# WGSwitch.net
KiCad netlist of a schematic drawn in EAGLE
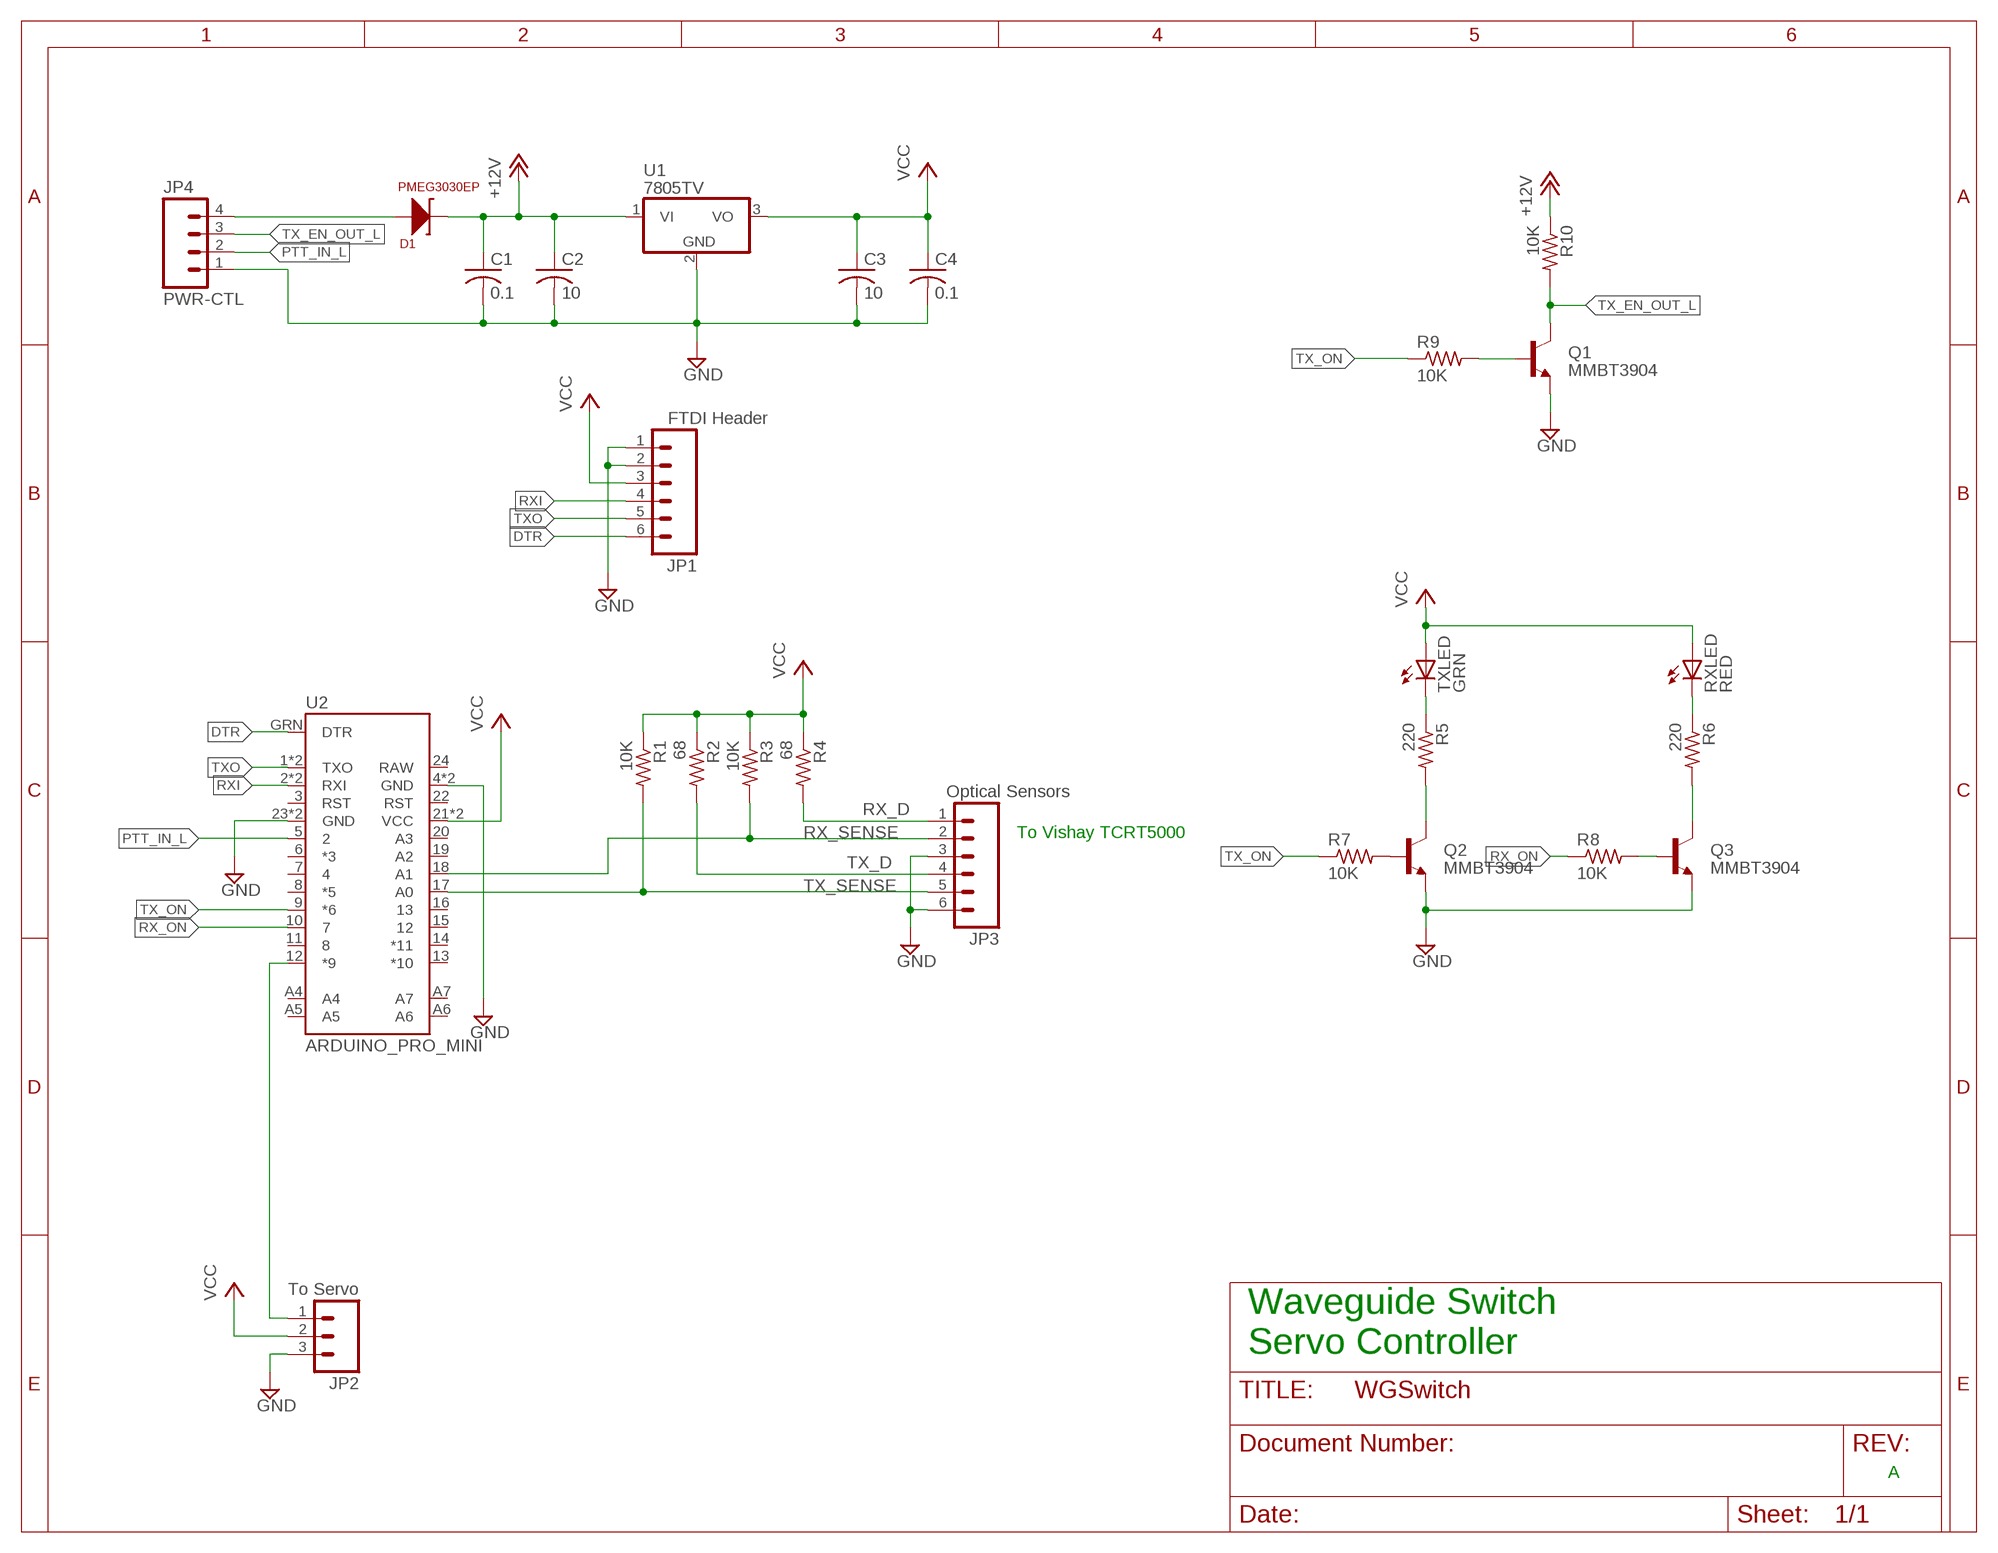
[diagram p0: schematic, sheet 1]

(export (version "E")
  (design (tool "Eeschema 10.0.6"))
  (components
    (comp (ref "C1")
      (value "0.1")
      (footprint "eagle-import:C0805K")
      (libsource (lib "eagle-import") (part "C-USC0805K"))
    )
    (comp (ref "C2")
      (value "10")
      (footprint "eagle-import:C1206K")
      (libsource (lib "eagle-import") (part "C-USC1206K"))
    )
    (comp (ref "C3")
      (value "10")
      (footprint "eagle-import:C1206K")
      (libsource (lib "eagle-import") (part "C-USC1206K"))
    )
    (comp (ref "C4")
      (value "0.1")
      (footprint "eagle-import:C0805K")
      (libsource (lib "eagle-import") (part "C-USC0805K"))
    )
    (comp (ref "D1")
      (value "PMEG3030EP")
      (footprint "eagle-import:SOD128")
      (libsource (lib "eagle-import") (part "PMEG3030EP"))
    )
    (comp (ref "JP1")
      (value "FTDI Header")
      (footprint "eagle-import:1X06")
      (libsource (lib "eagle-import") (part "M06SILK_FEMALE_PTH"))
    )
    (comp (ref "JP2")
      (value "To Servo")
      (footprint "eagle-import:1X03")
      (libsource (lib "eagle-import") (part "M03PTH"))
    )
    (comp (ref "JP3")
      (value "Optical Sensors")
      (footprint "eagle-import:1X06")
      (libsource (lib "eagle-import") (part "M06SILK_FEMALE_PTH"))
    )
    (comp (ref "JP4")
      (value "PWR-CTL")
      (footprint "eagle-import:1X04")
      (libsource (lib "eagle-import") (part "M04PTH"))
    )
    (comp (ref "Q1")
      (value "MMBT3904")
      (footprint "eagle-import:SOT23-3")
      (libsource (lib "eagle-import") (part "MMBT3904-HFSOT23-3"))
    )
    (comp (ref "Q2")
      (value "MMBT3904")
      (footprint "eagle-import:SOT23-3")
      (libsource (lib "eagle-import") (part "MMBT3904-HFSOT23-3"))
    )
    (comp (ref "Q3")
      (value "MMBT3904")
      (footprint "eagle-import:SOT23-3")
      (libsource (lib "eagle-import") (part "MMBT3904-HFSOT23-3"))
    )
    (comp (ref "R1")
      (value "10K")
      (footprint "eagle-import:R1206")
      (libsource (lib "eagle-import") (part "R-US_R1206"))
    )
    (comp (ref "R2")
      (value "68")
      (footprint "eagle-import:R1206")
      (libsource (lib "eagle-import") (part "R-US_R1206"))
    )
    (comp (ref "R3")
      (value "10K")
      (footprint "eagle-import:R1206")
      (libsource (lib "eagle-import") (part "R-US_R1206"))
    )
    (comp (ref "R4")
      (value "68")
      (footprint "eagle-import:R1206")
      (libsource (lib "eagle-import") (part "R-US_R1206"))
    )
    (comp (ref "R5")
      (value "220")
      (footprint "eagle-import:R1206")
      (libsource (lib "eagle-import") (part "R-US_R1206"))
    )
    (comp (ref "R6")
      (value "220")
      (footprint "eagle-import:R1206")
      (libsource (lib "eagle-import") (part "R-US_R1206"))
    )
    (comp (ref "R7")
      (value "10K")
      (footprint "eagle-import:R1206")
      (libsource (lib "eagle-import") (part "R-US_R1206"))
    )
    (comp (ref "R8")
      (value "10K")
      (footprint "eagle-import:R1206")
      (libsource (lib "eagle-import") (part "R-US_R1206"))
    )
    (comp (ref "R9")
      (value "10K")
      (footprint "eagle-import:R1206")
      (libsource (lib "eagle-import") (part "R-US_R1206"))
    )
    (comp (ref "R10")
      (value "10K")
      (footprint "eagle-import:R1206")
      (libsource (lib "eagle-import") (part "R-US_R1206"))
    )
    (comp (ref "RXLED")
      (value "RED")
      (footprint "eagle-import:LED5MM")
      (libsource (lib "eagle-import") (part "LED5MM"))
    )
    (comp (ref "TXLED")
      (value "GRN")
      (footprint "eagle-import:LED5MM")
      (libsource (lib "eagle-import") (part "LED5MM"))
    )
    (comp (ref "U1")
      (value "7805TV")
      (footprint "eagle-import:TO220V")
      (libsource (lib "eagle-import") (part "78TV05"))
    )
    (comp (ref "U2")
      (value "ARDUINO_PRO_MINI")
      (footprint "eagle-import:ARDUINO_PRO_MINI")
      (libsource (lib "eagle-import") (part "ARDUINO_PRO_MINI"))
    )
  )
  (nets
    (net (code "1") (name "+12V") (class "Default")
      (node (ref "C1") (pin "1") (pinfunction "1_1") (pintype "passive"))
      (node (ref "C2") (pin "1") (pinfunction "1_1") (pintype "passive"))
      (node (ref "D1") (pin "P$2") (pinfunction "C_P$2") (pintype "bidirectional"))
      (node (ref "R10") (pin "1") (pinfunction "1_1") (pintype "passive"))
      (node (ref "U1") (pin "1") (pinfunction "VI_1") (pintype "input"))
    )
    (net (code "2") (name "/RX_D") (class "Default")
      (node (ref "JP3") (pin "1") (pinfunction "1_1") (pintype "passive"))
      (node (ref "R4") (pin "2") (pinfunction "2_2") (pintype "passive"))
    )
    (net (code "3") (name "/RX_SENSE") (class "Default")
      (node (ref "JP3") (pin "2") (pinfunction "2_2") (pintype "passive"))
      (node (ref "R3") (pin "2") (pinfunction "2_2") (pintype "passive"))
      (node (ref "U2") (pin "18") (pinfunction "A1_18") (pintype "bidirectional"))
    )
    (net (code "4") (name "/TX_D") (class "Default")
      (node (ref "JP3") (pin "4") (pinfunction "4_4") (pintype "passive"))
      (node (ref "R2") (pin "2") (pinfunction "2_2") (pintype "passive"))
    )
    (net (code "5") (name "/TX_SENSE") (class "Default")
      (node (ref "JP3") (pin "5") (pinfunction "5_5") (pintype "passive"))
      (node (ref "R1") (pin "2") (pinfunction "2_2") (pintype "passive"))
      (node (ref "U2") (pin "17") (pinfunction "A0_17") (pintype "bidirectional"))
    )
    (net (code "6") (name "DTR") (class "Default")
      (node (ref "JP1") (pin "6") (pinfunction "6_6") (pintype "passive"))
      (node (ref "U2") (pin "GRN") (pinfunction "DTR_GRN") (pintype "bidirectional"))
    )
    (net (code "7") (name "GND") (class "Default")
      (node (ref "C1") (pin "2") (pinfunction "2_2") (pintype "passive"))
      (node (ref "C2") (pin "2") (pinfunction "2_2") (pintype "passive"))
      (node (ref "C3") (pin "2") (pinfunction "2_2") (pintype "passive"))
      (node (ref "C4") (pin "2") (pinfunction "2_2") (pintype "passive"))
      (node (ref "JP1") (pin "1") (pinfunction "1_1") (pintype "passive"))
      (node (ref "JP1") (pin "2") (pinfunction "2_2") (pintype "passive"))
      (node (ref "JP2") (pin "3") (pinfunction "3_3") (pintype "passive"))
      (node (ref "JP3") (pin "3") (pinfunction "3_3") (pintype "passive"))
      (node (ref "JP3") (pin "6") (pinfunction "6_6") (pintype "passive"))
      (node (ref "JP4") (pin "1") (pinfunction "1_1") (pintype "passive"))
      (node (ref "Q1") (pin "2") (pinfunction "E_2") (pintype "passive"))
      (node (ref "Q2") (pin "2") (pinfunction "E_2") (pintype "passive"))
      (node (ref "Q3") (pin "2") (pinfunction "E_2") (pintype "passive"))
      (node (ref "U1") (pin "2") (pinfunction "GND_2") (pintype "passive"))
      (node (ref "U2") (pin "23") (pinfunction "GND_23") (pintype "bidirectional"))
      (node (ref "U2") (pin "4") (pinfunction "GND_4") (pintype "bidirectional"))
      (node (ref "U2") (pin "BLK") (pinfunction "GND_BLK") (pintype "bidirectional"))
      (node (ref "U2") (pin "GND") (pinfunction "GND_GND") (pintype "bidirectional"))
    )
    (net (code "8") (name "Net-(D1-A)") (class "Default")
      (node (ref "D1") (pin "P$1") (pinfunction "A_P$1") (pintype "bidirectional"))
      (node (ref "JP4") (pin "4") (pinfunction "4_4") (pintype "passive"))
    )
    (net (code "9") (name "Net-(Q1-B)") (class "Default")
      (node (ref "Q1") (pin "1") (pinfunction "B_1") (pintype "passive"))
      (node (ref "R9") (pin "2") (pinfunction "2_2") (pintype "passive"))
    )
    (net (code "10") (name "Net-(Q2-B)") (class "Default")
      (node (ref "Q2") (pin "1") (pinfunction "B_1") (pintype "passive"))
      (node (ref "R7") (pin "2") (pinfunction "2_2") (pintype "passive"))
    )
    (net (code "11") (name "Net-(Q2-C)") (class "Default")
      (node (ref "Q2") (pin "3") (pinfunction "C_3") (pintype "passive"))
      (node (ref "R5") (pin "2") (pinfunction "2_2") (pintype "passive"))
    )
    (net (code "12") (name "Net-(Q3-B)") (class "Default")
      (node (ref "Q3") (pin "1") (pinfunction "B_1") (pintype "passive"))
      (node (ref "R8") (pin "2") (pinfunction "2_2") (pintype "passive"))
    )
    (net (code "13") (name "Net-(Q3-C)") (class "Default")
      (node (ref "Q3") (pin "3") (pinfunction "C_3") (pintype "passive"))
      (node (ref "R6") (pin "2") (pinfunction "2_2") (pintype "passive"))
    )
    (net (code "14") (name "Net-(RXLED-C)") (class "Default")
      (node (ref "R6") (pin "1") (pinfunction "1_1") (pintype "passive"))
      (node (ref "RXLED") (pin "K") (pinfunction "C_K") (pintype "passive"))
    )
    (net (code "15") (name "Net-(TXLED-C)") (class "Default")
      (node (ref "R5") (pin "1") (pinfunction "1_1") (pintype "passive"))
      (node (ref "TXLED") (pin "K") (pinfunction "C_K") (pintype "passive"))
    )
    (net (code "16") (name "Net-(U2-*9)") (class "Default")
      (node (ref "JP2") (pin "1") (pinfunction "1_1") (pintype "passive"))
      (node (ref "U2") (pin "12") (pinfunction "*9_12") (pintype "bidirectional"))
    )
    (net (code "17") (name "PTT_IN_L") (class "Default")
      (node (ref "JP4") (pin "2") (pinfunction "2_2") (pintype "passive"))
      (node (ref "U2") (pin "5") (pinfunction "2_5") (pintype "bidirectional"))
    )
    (net (code "18") (name "RXI") (class "Default")
      (node (ref "JP1") (pin "4") (pinfunction "4_4") (pintype "passive"))
      (node (ref "U2") (pin "2") (pinfunction "RXI_2") (pintype "bidirectional"))
      (node (ref "U2") (pin "RXI") (pinfunction "RXI_RXI") (pintype "bidirectional"))
    )
    (net (code "19") (name "RX_ON") (class "Default")
      (node (ref "R8") (pin "1") (pinfunction "1_1") (pintype "passive"))
      (node (ref "U2") (pin "10") (pinfunction "7_10") (pintype "bidirectional"))
    )
    (net (code "20") (name "TXO") (class "Default")
      (node (ref "JP1") (pin "5") (pinfunction "5_5") (pintype "passive"))
      (node (ref "U2") (pin "1") (pinfunction "TXO_1") (pintype "bidirectional"))
      (node (ref "U2") (pin "TXO") (pinfunction "TXO_TXO") (pintype "bidirectional"))
    )
    (net (code "21") (name "TX_EN_OUT_L") (class "Default")
      (node (ref "JP4") (pin "3") (pinfunction "3_3") (pintype "passive"))
      (node (ref "Q1") (pin "3") (pinfunction "C_3") (pintype "passive"))
      (node (ref "R10") (pin "2") (pinfunction "2_2") (pintype "passive"))
    )
    (net (code "22") (name "TX_ON") (class "Default")
      (node (ref "R7") (pin "1") (pinfunction "1_1") (pintype "passive"))
      (node (ref "R9") (pin "1") (pinfunction "1_1") (pintype "passive"))
      (node (ref "U2") (pin "9") (pinfunction "*6_9") (pintype "bidirectional"))
    )
    (net (code "23") (name "VCC") (class "Default")
      (node (ref "C3") (pin "1") (pinfunction "1_1") (pintype "passive"))
      (node (ref "C4") (pin "1") (pinfunction "1_1") (pintype "passive"))
      (node (ref "JP1") (pin "3") (pinfunction "3_3") (pintype "passive"))
      (node (ref "JP2") (pin "2") (pinfunction "2_2") (pintype "passive"))
      (node (ref "R1") (pin "1") (pinfunction "1_1") (pintype "passive"))
      (node (ref "R2") (pin "1") (pinfunction "1_1") (pintype "passive"))
      (node (ref "R3") (pin "1") (pinfunction "1_1") (pintype "passive"))
      (node (ref "R4") (pin "1") (pinfunction "1_1") (pintype "passive"))
      (node (ref "RXLED") (pin "A") (pinfunction "A_A") (pintype "passive"))
      (node (ref "TXLED") (pin "A") (pinfunction "A_A") (pintype "passive"))
      (node (ref "U1") (pin "3") (pinfunction "VO_3") (pintype "passive"))
      (node (ref "U2") (pin "21") (pinfunction "VCC_21") (pintype "bidirectional"))
      (node (ref "U2") (pin "VCC") (pinfunction "VCC_VCC") (pintype "bidirectional"))
    )
    (net (code "24") (name "unconnected-(U2-*3-Pad6)") (class "Default")
      (node (ref "U2") (pin "6") (pinfunction "*3_6") (pintype "bidirectional"))
    )
    (net (code "25") (name "unconnected-(U2-*5-Pad8)") (class "Default")
      (node (ref "U2") (pin "8") (pinfunction "*5_8") (pintype "bidirectional"))
    )
    (net (code "26") (name "unconnected-(U2-*10-Pad13)") (class "Default")
      (node (ref "U2") (pin "13") (pinfunction "*10_13") (pintype "bidirectional"))
    )
    (net (code "27") (name "unconnected-(U2-*11-Pad14)") (class "Default")
      (node (ref "U2") (pin "14") (pinfunction "*11_14") (pintype "bidirectional"))
    )
    (net (code "28") (name "unconnected-(U2-4-Pad7)") (class "Default")
      (node (ref "U2") (pin "7") (pinfunction "4_7") (pintype "bidirectional"))
    )
    (net (code "29") (name "unconnected-(U2-8-Pad11)") (class "Default")
      (node (ref "U2") (pin "11") (pinfunction "8_11") (pintype "bidirectional"))
    )
    (net (code "30") (name "unconnected-(U2-12-Pad15)") (class "Default")
      (node (ref "U2") (pin "15") (pinfunction "12_15") (pintype "bidirectional"))
    )
    (net (code "31") (name "unconnected-(U2-13-Pad16)") (class "Default")
      (node (ref "U2") (pin "16") (pinfunction "13_16") (pintype "bidirectional"))
    )
    (net (code "32") (name "unconnected-(U2-A2-Pad19)") (class "Default")
      (node (ref "U2") (pin "19") (pinfunction "A2_19") (pintype "bidirectional"))
    )
    (net (code "33") (name "unconnected-(U2-A3-Pad20)") (class "Default")
      (node (ref "U2") (pin "20") (pinfunction "A3_20") (pintype "bidirectional"))
    )
    (net (code "34") (name "unconnected-(U2-PadA4)") (class "Default")
      (node (ref "U2") (pin "A4") (pinfunction "A4_A4") (pintype "bidirectional"))
    )
    (net (code "35") (name "unconnected-(U2-PadA5)") (class "Default")
      (node (ref "U2") (pin "A5") (pinfunction "A5_A5") (pintype "bidirectional"))
    )
    (net (code "36") (name "unconnected-(U2-PadA6)") (class "Default")
      (node (ref "U2") (pin "A6") (pinfunction "A6_A6") (pintype "bidirectional"))
    )
    (net (code "37") (name "unconnected-(U2-PadA7)") (class "Default")
      (node (ref "U2") (pin "A7") (pinfunction "A7_A7") (pintype "bidirectional"))
    )
    (net (code "38") (name "unconnected-(U2-RAW-Pad24)") (class "Default")
      (node (ref "U2") (pin "24") (pinfunction "RAW_24") (pintype "bidirectional"))
    )
    (net (code "39") (name "unconnected-(U2-RST-Pad3)") (class "Default")
      (node (ref "U2") (pin "3") (pinfunction "RST_3") (pintype "bidirectional"))
    )
    (net (code "40") (name "unconnected-(U2-RST-Pad22)") (class "Default")
      (node (ref "U2") (pin "22") (pinfunction "RST_22") (pintype "bidirectional"))
    )
  )
)
